# Laser_Array_Temp_V1_2.net
KiCad netlist of a schematic drawn in EAGLE
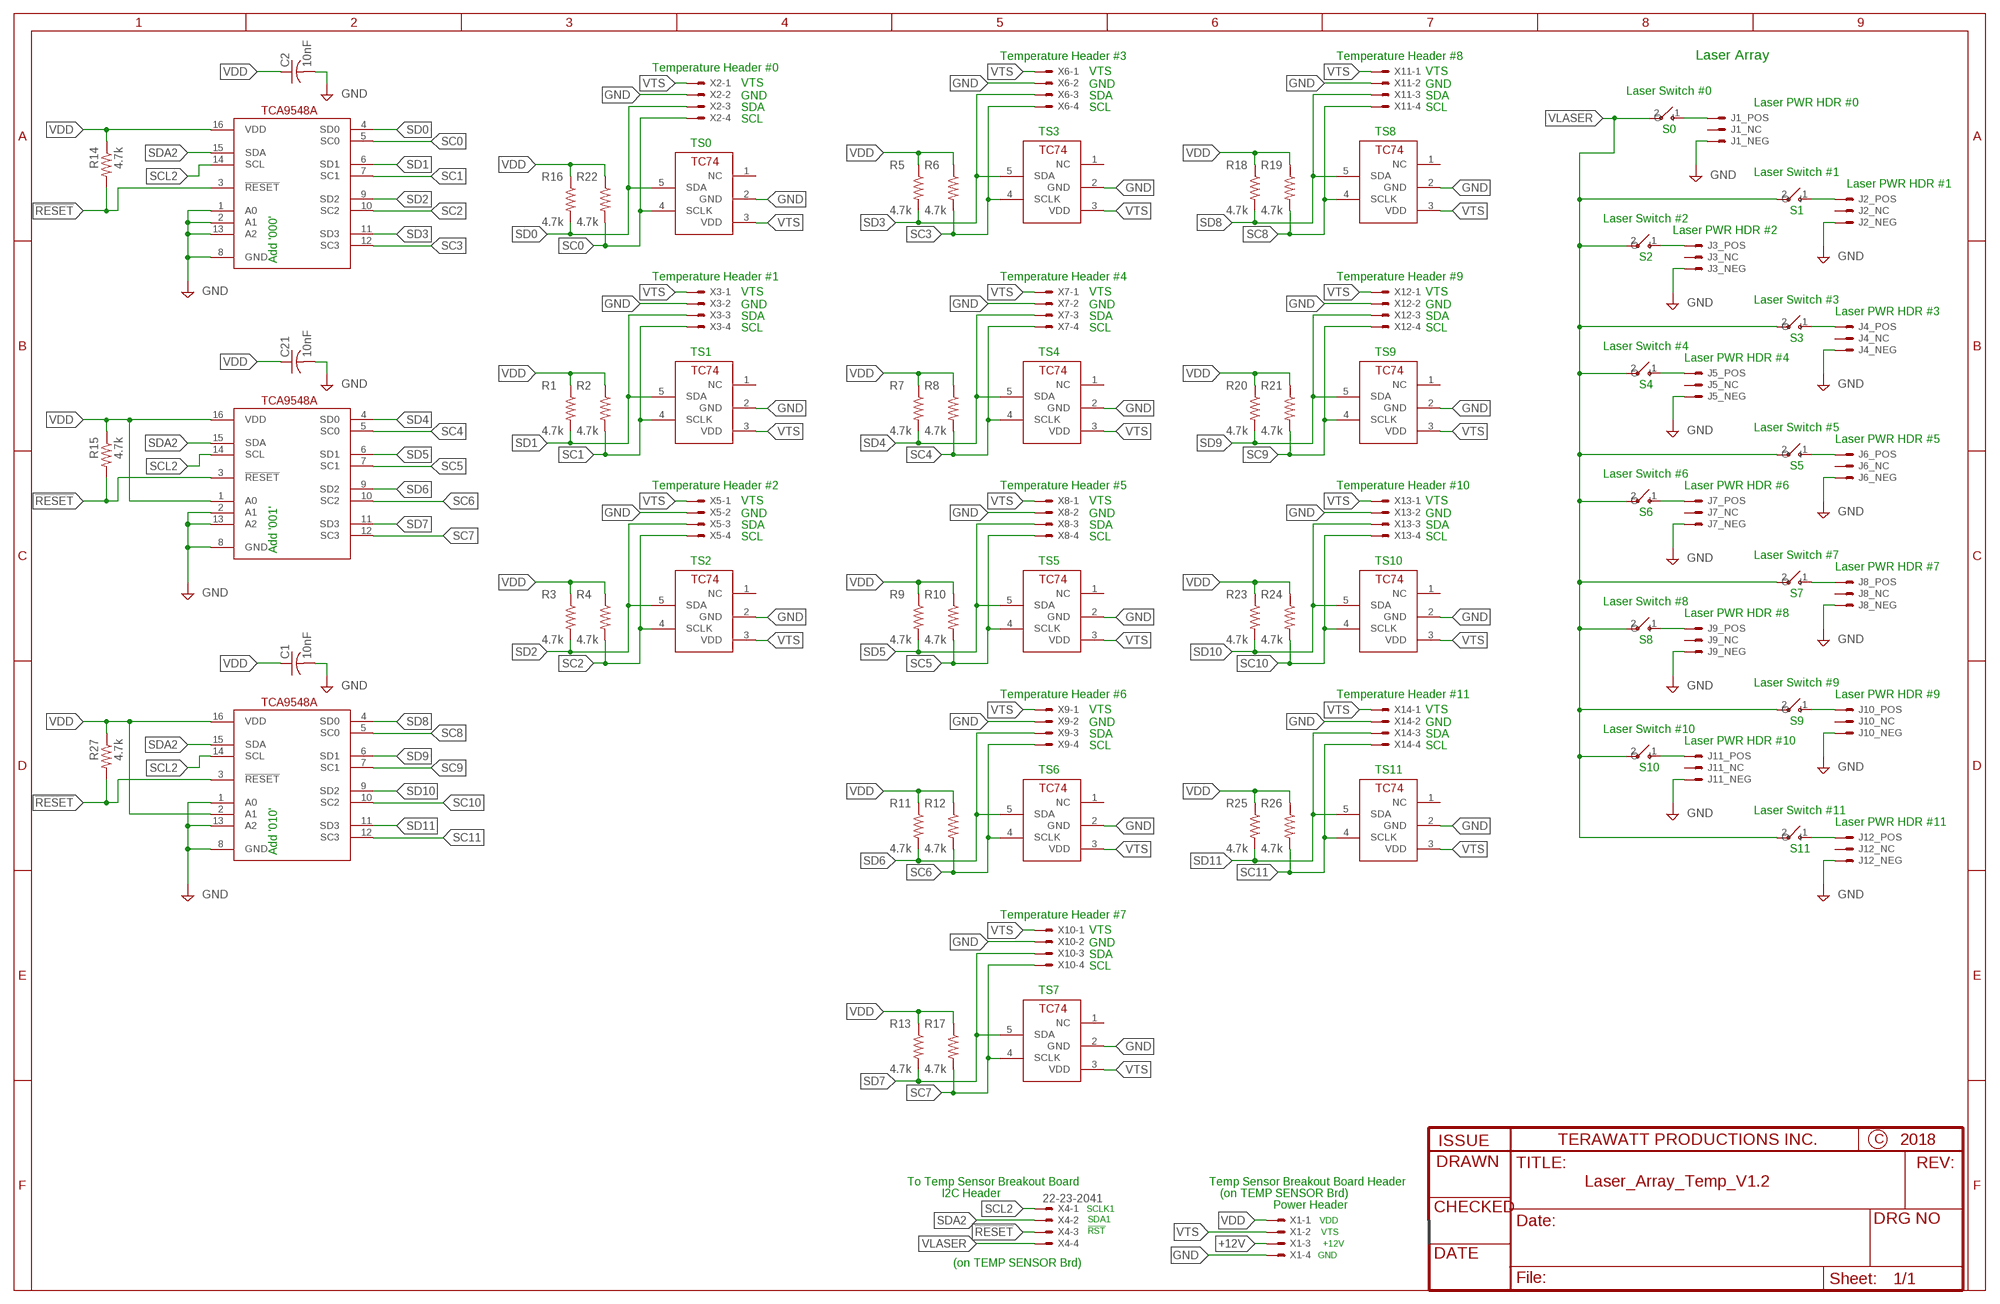
[diagram p0: schematic, sheet 1]

(export (version "E")
  (design (tool "Eeschema 10.0.6"))
  (components
    (comp (ref "C1")
      (value "10nF")
      (footprint "eagle-import:C0805")
      (libsource (lib "eagle-import") (part "C-USC0805"))
    )
    (comp (ref "C2")
      (value "10nF")
      (footprint "eagle-import:C0805")
      (libsource (lib "eagle-import") (part "C-USC0805"))
    )
    (comp (ref "C21")
      (value "10nF")
      (footprint "eagle-import:C0805")
      (libsource (lib "eagle-import") (part "C-USC0805"))
    )
    (comp (ref "J1")
      (value "LASER_MOD")
      (footprint "eagle-import:LASER_MOD")
      (libsource (lib "eagle-import") (part "LASER_MOD"))
    )
    (comp (ref "J2")
      (value "LASER_MOD")
      (footprint "eagle-import:LASER_MOD")
      (libsource (lib "eagle-import") (part "LASER_MOD"))
    )
    (comp (ref "J3")
      (value "LASER_MOD")
      (footprint "eagle-import:LASER_MOD")
      (libsource (lib "eagle-import") (part "LASER_MOD"))
    )
    (comp (ref "J4")
      (value "LASER_MOD")
      (footprint "eagle-import:LASER_MOD")
      (libsource (lib "eagle-import") (part "LASER_MOD"))
    )
    (comp (ref "J5")
      (value "LASER_MOD")
      (footprint "eagle-import:LASER_MOD")
      (libsource (lib "eagle-import") (part "LASER_MOD"))
    )
    (comp (ref "J6")
      (value "LASER_MOD")
      (footprint "eagle-import:LASER_MOD")
      (libsource (lib "eagle-import") (part "LASER_MOD"))
    )
    (comp (ref "J7")
      (value "LASER_MOD")
      (footprint "eagle-import:LASER_MOD")
      (libsource (lib "eagle-import") (part "LASER_MOD"))
    )
    (comp (ref "J8")
      (value "LASER_MOD")
      (footprint "eagle-import:LASER_MOD")
      (libsource (lib "eagle-import") (part "LASER_MOD"))
    )
    (comp (ref "J9")
      (value "LASER_MOD")
      (footprint "eagle-import:LASER_MOD")
      (libsource (lib "eagle-import") (part "LASER_MOD"))
    )
    (comp (ref "J10")
      (value "LASER_MOD")
      (footprint "eagle-import:LASER_MOD")
      (libsource (lib "eagle-import") (part "LASER_MOD"))
    )
    (comp (ref "J11")
      (value "LASER_MOD")
      (footprint "eagle-import:LASER_MOD")
      (libsource (lib "eagle-import") (part "LASER_MOD"))
    )
    (comp (ref "J12")
      (value "LASER_MOD")
      (footprint "eagle-import:LASER_MOD")
      (libsource (lib "eagle-import") (part "LASER_MOD"))
    )
    (comp (ref "R1")
      (value "4.7k")
      (footprint "eagle-import:M0805")
      (libsource (lib "eagle-import") (part "R-US_M0805"))
    )
    (comp (ref "R2")
      (value "4.7k")
      (footprint "eagle-import:M0805")
      (libsource (lib "eagle-import") (part "R-US_M0805"))
    )
    (comp (ref "R3")
      (value "4.7k")
      (footprint "eagle-import:M0805")
      (libsource (lib "eagle-import") (part "R-US_M0805"))
    )
    (comp (ref "R4")
      (value "4.7k")
      (footprint "eagle-import:M0805")
      (libsource (lib "eagle-import") (part "R-US_M0805"))
    )
    (comp (ref "R5")
      (value "4.7k")
      (footprint "eagle-import:M0805")
      (libsource (lib "eagle-import") (part "R-US_M0805"))
    )
    (comp (ref "R6")
      (value "4.7k")
      (footprint "eagle-import:M0805")
      (libsource (lib "eagle-import") (part "R-US_M0805"))
    )
    (comp (ref "R7")
      (value "4.7k")
      (footprint "eagle-import:M0805")
      (libsource (lib "eagle-import") (part "R-US_M0805"))
    )
    (comp (ref "R8")
      (value "4.7k")
      (footprint "eagle-import:M0805")
      (libsource (lib "eagle-import") (part "R-US_M0805"))
    )
    (comp (ref "R9")
      (value "4.7k")
      (footprint "eagle-import:M0805")
      (libsource (lib "eagle-import") (part "R-US_M0805"))
    )
    (comp (ref "R10")
      (value "4.7k")
      (footprint "eagle-import:M0805")
      (libsource (lib "eagle-import") (part "R-US_M0805"))
    )
    (comp (ref "R11")
      (value "4.7k")
      (footprint "eagle-import:M0805")
      (libsource (lib "eagle-import") (part "R-US_M0805"))
    )
    (comp (ref "R12")
      (value "4.7k")
      (footprint "eagle-import:M0805")
      (libsource (lib "eagle-import") (part "R-US_M0805"))
    )
    (comp (ref "R13")
      (value "4.7k")
      (footprint "eagle-import:M0805")
      (libsource (lib "eagle-import") (part "R-US_M0805"))
    )
    (comp (ref "R14")
      (value "4.7k")
      (footprint "eagle-import:M0805")
      (libsource (lib "eagle-import") (part "R-US_M0805"))
    )
    (comp (ref "R15")
      (value "4.7k")
      (footprint "eagle-import:M0805")
      (libsource (lib "eagle-import") (part "R-US_M0805"))
    )
    (comp (ref "R16")
      (value "4.7k")
      (footprint "eagle-import:M0805")
      (libsource (lib "eagle-import") (part "R-US_M0805"))
    )
    (comp (ref "R17")
      (value "4.7k")
      (footprint "eagle-import:M0805")
      (libsource (lib "eagle-import") (part "R-US_M0805"))
    )
    (comp (ref "R18")
      (value "4.7k")
      (footprint "eagle-import:M0805")
      (libsource (lib "eagle-import") (part "R-US_M0805"))
    )
    (comp (ref "R19")
      (value "4.7k")
      (footprint "eagle-import:M0805")
      (libsource (lib "eagle-import") (part "R-US_M0805"))
    )
    (comp (ref "R20")
      (value "4.7k")
      (footprint "eagle-import:M0805")
      (libsource (lib "eagle-import") (part "R-US_M0805"))
    )
    (comp (ref "R21")
      (value "4.7k")
      (footprint "eagle-import:M0805")
      (libsource (lib "eagle-import") (part "R-US_M0805"))
    )
    (comp (ref "R22")
      (value "4.7k")
      (footprint "eagle-import:M0805")
      (libsource (lib "eagle-import") (part "R-US_M0805"))
    )
    (comp (ref "R23")
      (value "4.7k")
      (footprint "eagle-import:M0805")
      (libsource (lib "eagle-import") (part "R-US_M0805"))
    )
    (comp (ref "R24")
      (value "4.7k")
      (footprint "eagle-import:M0805")
      (libsource (lib "eagle-import") (part "R-US_M0805"))
    )
    (comp (ref "R25")
      (value "4.7k")
      (footprint "eagle-import:M0805")
      (libsource (lib "eagle-import") (part "R-US_M0805"))
    )
    (comp (ref "R26")
      (value "4.7k")
      (footprint "eagle-import:M0805")
      (libsource (lib "eagle-import") (part "R-US_M0805"))
    )
    (comp (ref "R27")
      (value "4.7k")
      (footprint "eagle-import:M0805")
      (libsource (lib "eagle-import") (part "R-US_M0805"))
    )
    (comp (ref "S13")
      (value "TOGGLE_SPST")
      (footprint "eagle-import:22-23-2021")
      (libsource (lib "eagle-import") (part "TOGGLE_SPST"))
    )
    (comp (ref "S14")
      (value "TOGGLE_SPST")
      (footprint "eagle-import:22-23-2021")
      (libsource (lib "eagle-import") (part "TOGGLE_SPST"))
    )
    (comp (ref "S15")
      (value "TOGGLE_SPST")
      (footprint "eagle-import:22-23-2021")
      (libsource (lib "eagle-import") (part "TOGGLE_SPST"))
    )
    (comp (ref "S16")
      (value "TOGGLE_SPST")
      (footprint "eagle-import:22-23-2021")
      (libsource (lib "eagle-import") (part "TOGGLE_SPST"))
    )
    (comp (ref "S17")
      (value "TOGGLE_SPST")
      (footprint "eagle-import:22-23-2021")
      (libsource (lib "eagle-import") (part "TOGGLE_SPST"))
    )
    (comp (ref "S18")
      (value "TOGGLE_SPST")
      (footprint "eagle-import:22-23-2021")
      (libsource (lib "eagle-import") (part "TOGGLE_SPST"))
    )
    (comp (ref "S19")
      (value "TOGGLE_SPST")
      (footprint "eagle-import:22-23-2021")
      (libsource (lib "eagle-import") (part "TOGGLE_SPST"))
    )
    (comp (ref "S20")
      (value "TOGGLE_SPST")
      (footprint "eagle-import:22-23-2021")
      (libsource (lib "eagle-import") (part "TOGGLE_SPST"))
    )
    (comp (ref "S21")
      (value "TOGGLE_SPST")
      (footprint "eagle-import:22-23-2021")
      (libsource (lib "eagle-import") (part "TOGGLE_SPST"))
    )
    (comp (ref "S22")
      (value "TOGGLE_SPST")
      (footprint "eagle-import:22-23-2021")
      (libsource (lib "eagle-import") (part "TOGGLE_SPST"))
    )
    (comp (ref "S23")
      (value "TOGGLE_SPST")
      (footprint "eagle-import:22-23-2021")
      (libsource (lib "eagle-import") (part "TOGGLE_SPST"))
    )
    (comp (ref "S24")
      (value "TOGGLE_SPST")
      (footprint "eagle-import:22-23-2021")
      (libsource (lib "eagle-import") (part "TOGGLE_SPST"))
    )
    (comp (ref "TS1")
      (value "TC74")
      (footprint "eagle-import:SOT23-5L")
      (libsource (lib "eagle-import") (part "TC74"))
    )
    (comp (ref "TS2")
      (value "TC74")
      (footprint "eagle-import:SOT23-5L")
      (libsource (lib "eagle-import") (part "TC74"))
    )
    (comp (ref "TS3")
      (value "TC74")
      (footprint "eagle-import:SOT23-5L")
      (libsource (lib "eagle-import") (part "TC74"))
    )
    (comp (ref "TS4")
      (value "TC74")
      (footprint "eagle-import:SOT23-5L")
      (libsource (lib "eagle-import") (part "TC74"))
    )
    (comp (ref "TS5")
      (value "TC74")
      (footprint "eagle-import:SOT23-5L")
      (libsource (lib "eagle-import") (part "TC74"))
    )
    (comp (ref "TS6")
      (value "TC74")
      (footprint "eagle-import:SOT23-5L")
      (libsource (lib "eagle-import") (part "TC74"))
    )
    (comp (ref "TS7")
      (value "TC74")
      (footprint "eagle-import:SOT23-5L")
      (libsource (lib "eagle-import") (part "TC74"))
    )
    (comp (ref "TS8")
      (value "TC74")
      (footprint "eagle-import:SOT23-5L")
      (libsource (lib "eagle-import") (part "TC74"))
    )
    (comp (ref "TS9")
      (value "TC74")
      (footprint "eagle-import:SOT23-5L")
      (libsource (lib "eagle-import") (part "TC74"))
    )
    (comp (ref "TS10")
      (value "TC74")
      (footprint "eagle-import:SOT23-5L")
      (libsource (lib "eagle-import") (part "TC74"))
    )
    (comp (ref "TS11")
      (value "TC74")
      (footprint "eagle-import:SOT23-5L")
      (libsource (lib "eagle-import") (part "TC74"))
    )
    (comp (ref "TS12")
      (value "TC74")
      (footprint "eagle-import:SOT23-5L")
      (libsource (lib "eagle-import") (part "TC74"))
    )
    (comp (ref "U1")
      (value "TCA9546A")
      (footprint "eagle-import:SOIC16N")
      (libsource (lib "eagle-import") (part "TCA9546A"))
    )
    (comp (ref "U2")
      (value "TCA9546A")
      (footprint "eagle-import:SOIC16N")
      (libsource (lib "eagle-import") (part "TCA9546A"))
    )
    (comp (ref "U3")
      (value "TCA9546A")
      (footprint "eagle-import:SOIC16N")
      (libsource (lib "eagle-import") (part "TCA9546A"))
    )
    (comp (ref "X1")
      (value "22-23-2041")
      (footprint "eagle-import:22-23-2041")
      (fields (field (name "MF") "MOLEX"))
      (libsource (lib "eagle-import") (part "22-23-2041"))
    )
    (comp (ref "X2")
      (value "22-23-2041")
      (footprint "eagle-import:22-23-2041")
      (fields (field (name "MF") "MOLEX"))
      (libsource (lib "eagle-import") (part "22-23-2041"))
    )
    (comp (ref "X3")
      (value "22-23-2041")
      (footprint "eagle-import:22-23-2041")
      (fields (field (name "MF") "MOLEX"))
      (libsource (lib "eagle-import") (part "22-23-2041"))
    )
    (comp (ref "X4")
      (value "22-23-2041")
      (footprint "eagle-import:22-23-2041")
      (fields (field (name "MF") "MOLEX"))
      (libsource (lib "eagle-import") (part "22-23-2041"))
    )
    (comp (ref "X5")
      (value "22-23-2041")
      (footprint "eagle-import:22-23-2041")
      (fields (field (name "MF") "MOLEX"))
      (libsource (lib "eagle-import") (part "22-23-2041"))
    )
    (comp (ref "X6")
      (value "22-23-2041")
      (footprint "eagle-import:22-23-2041")
      (fields (field (name "MF") "MOLEX"))
      (libsource (lib "eagle-import") (part "22-23-2041"))
    )
    (comp (ref "X7")
      (value "22-23-2041")
      (footprint "eagle-import:22-23-2041")
      (fields (field (name "MF") "MOLEX"))
      (libsource (lib "eagle-import") (part "22-23-2041"))
    )
    (comp (ref "X8")
      (value "22-23-2041")
      (footprint "eagle-import:22-23-2041")
      (fields (field (name "MF") "MOLEX"))
      (libsource (lib "eagle-import") (part "22-23-2041"))
    )
    (comp (ref "X9")
      (value "22-23-2041")
      (footprint "eagle-import:22-23-2041")
      (fields (field (name "MF") "MOLEX"))
      (libsource (lib "eagle-import") (part "22-23-2041"))
    )
    (comp (ref "X10")
      (value "22-23-2041")
      (footprint "eagle-import:22-23-2041")
      (fields (field (name "MF") "MOLEX"))
      (libsource (lib "eagle-import") (part "22-23-2041"))
    )
    (comp (ref "X11")
      (value "22-23-2041")
      (footprint "eagle-import:22-23-2041")
      (fields (field (name "MF") "MOLEX"))
      (libsource (lib "eagle-import") (part "22-23-2041"))
    )
    (comp (ref "X12")
      (value "22-23-2041")
      (footprint "eagle-import:22-23-2041")
      (fields (field (name "MF") "MOLEX"))
      (libsource (lib "eagle-import") (part "22-23-2041"))
    )
    (comp (ref "X13")
      (value "22-23-2041")
      (footprint "eagle-import:22-23-2041")
      (fields (field (name "MF") "MOLEX"))
      (libsource (lib "eagle-import") (part "22-23-2041"))
    )
    (comp (ref "X14")
      (value "22-23-2041")
      (footprint "eagle-import:22-23-2041")
      (fields (field (name "MF") "MOLEX"))
      (libsource (lib "eagle-import") (part "22-23-2041"))
    )
  )
  (nets
    (net (code "1") (name "+12V") (class "Default")
      (node (ref "X1") (pin "3") (pinfunction "S_3") (pintype "passive"))
    )
    (net (code "2") (name "/~{RESET}") (class "Default")
      (node (ref "R14") (pin "2") (pinfunction "2_2") (pintype "passive"))
      (node (ref "R15") (pin "2") (pinfunction "2_2") (pintype "passive"))
      (node (ref "R27") (pin "2") (pinfunction "2_2") (pintype "passive"))
      (node (ref "U1") (pin "3") (pinfunction "~{RESET}_3") (pintype "bidirectional"))
      (node (ref "U2") (pin "3") (pinfunction "~{RESET}_3") (pintype "bidirectional"))
      (node (ref "U3") (pin "3") (pinfunction "~{RESET}_3") (pintype "bidirectional"))
      (node (ref "X4") (pin "3") (pinfunction "S_3") (pintype "passive"))
    )
    (net (code "3") (name "GND") (class "Default")
      (node (ref "C1") (pin "2") (pinfunction "2_2") (pintype "passive"))
      (node (ref "C2") (pin "2") (pinfunction "2_2") (pintype "passive"))
      (node (ref "C21") (pin "2") (pinfunction "2_2") (pintype "passive"))
      (node (ref "J1") (pin "3") (pinfunction "S_3") (pintype "passive"))
      (node (ref "J10") (pin "3") (pinfunction "S_3") (pintype "passive"))
      (node (ref "J11") (pin "3") (pinfunction "S_3") (pintype "passive"))
      (node (ref "J12") (pin "3") (pinfunction "S_3") (pintype "passive"))
      (node (ref "J2") (pin "3") (pinfunction "S_3") (pintype "passive"))
      (node (ref "J3") (pin "3") (pinfunction "S_3") (pintype "passive"))
      (node (ref "J4") (pin "3") (pinfunction "S_3") (pintype "passive"))
      (node (ref "J5") (pin "3") (pinfunction "S_3") (pintype "passive"))
      (node (ref "J6") (pin "3") (pinfunction "S_3") (pintype "passive"))
      (node (ref "J7") (pin "3") (pinfunction "S_3") (pintype "passive"))
      (node (ref "J8") (pin "3") (pinfunction "S_3") (pintype "passive"))
      (node (ref "J9") (pin "3") (pinfunction "S_3") (pintype "passive"))
      (node (ref "TS1") (pin "2") (pinfunction "GND_2") (pintype "bidirectional"))
      (node (ref "TS10") (pin "2") (pinfunction "GND_2") (pintype "bidirectional"))
      (node (ref "TS11") (pin "2") (pinfunction "GND_2") (pintype "bidirectional"))
      (node (ref "TS12") (pin "2") (pinfunction "GND_2") (pintype "bidirectional"))
      (node (ref "TS2") (pin "2") (pinfunction "GND_2") (pintype "bidirectional"))
      (node (ref "TS3") (pin "2") (pinfunction "GND_2") (pintype "bidirectional"))
      (node (ref "TS4") (pin "2") (pinfunction "GND_2") (pintype "bidirectional"))
      (node (ref "TS5") (pin "2") (pinfunction "GND_2") (pintype "bidirectional"))
      (node (ref "TS6") (pin "2") (pinfunction "GND_2") (pintype "bidirectional"))
      (node (ref "TS7") (pin "2") (pinfunction "GND_2") (pintype "bidirectional"))
      (node (ref "TS8") (pin "2") (pinfunction "GND_2") (pintype "bidirectional"))
      (node (ref "TS9") (pin "2") (pinfunction "GND_2") (pintype "bidirectional"))
      (node (ref "U1") (pin "1") (pinfunction "A0_1") (pintype "bidirectional"))
      (node (ref "U1") (pin "13") (pinfunction "A2_13") (pintype "bidirectional"))
      (node (ref "U1") (pin "2") (pinfunction "A1_2") (pintype "bidirectional"))
      (node (ref "U1") (pin "8") (pinfunction "GND_8") (pintype "bidirectional"))
      (node (ref "U2") (pin "13") (pinfunction "A2_13") (pintype "bidirectional"))
      (node (ref "U2") (pin "2") (pinfunction "A1_2") (pintype "bidirectional"))
      (node (ref "U2") (pin "8") (pinfunction "GND_8") (pintype "bidirectional"))
      (node (ref "U3") (pin "1") (pinfunction "A0_1") (pintype "bidirectional"))
      (node (ref "U3") (pin "13") (pinfunction "A2_13") (pintype "bidirectional"))
      (node (ref "U3") (pin "8") (pinfunction "GND_8") (pintype "bidirectional"))
      (node (ref "X1") (pin "4") (pinfunction "S_4") (pintype "passive"))
      (node (ref "X10") (pin "2") (pinfunction "S_2") (pintype "passive"))
      (node (ref "X11") (pin "2") (pinfunction "S_2") (pintype "passive"))
      (node (ref "X12") (pin "2") (pinfunction "S_2") (pintype "passive"))
      (node (ref "X13") (pin "2") (pinfunction "S_2") (pintype "passive"))
      (node (ref "X14") (pin "2") (pinfunction "S_2") (pintype "passive"))
      (node (ref "X2") (pin "2") (pinfunction "S_2") (pintype "passive"))
      (node (ref "X3") (pin "2") (pinfunction "S_2") (pintype "passive"))
      (node (ref "X5") (pin "2") (pinfunction "S_2") (pintype "passive"))
      (node (ref "X6") (pin "2") (pinfunction "S_2") (pintype "passive"))
      (node (ref "X7") (pin "2") (pinfunction "S_2") (pintype "passive"))
      (node (ref "X8") (pin "2") (pinfunction "S_2") (pintype "passive"))
      (node (ref "X9") (pin "2") (pinfunction "S_2") (pintype "passive"))
    )
    (net (code "4") (name "Net-(J1C-S)") (class "Default")
      (node (ref "J1") (pin "1") (pinfunction "S_1") (pintype "passive"))
      (node (ref "S16") (pin "1") (pinfunction "O_1") (pintype "bidirectional"))
    )
    (net (code "5") (name "Net-(J2C-S)") (class "Default")
      (node (ref "J2") (pin "1") (pinfunction "S_1") (pintype "passive"))
      (node (ref "S13") (pin "1") (pinfunction "O_1") (pintype "bidirectional"))
    )
    (net (code "6") (name "Net-(J3C-S)") (class "Default")
      (node (ref "J3") (pin "1") (pinfunction "S_1") (pintype "passive"))
      (node (ref "S14") (pin "1") (pinfunction "O_1") (pintype "bidirectional"))
    )
    (net (code "7") (name "Net-(J4C-S)") (class "Default")
      (node (ref "J4") (pin "1") (pinfunction "S_1") (pintype "passive"))
      (node (ref "S15") (pin "1") (pinfunction "O_1") (pintype "bidirectional"))
    )
    (net (code "8") (name "Net-(J5C-S)") (class "Default")
      (node (ref "J5") (pin "1") (pinfunction "S_1") (pintype "passive"))
      (node (ref "S17") (pin "1") (pinfunction "O_1") (pintype "bidirectional"))
    )
    (net (code "9") (name "Net-(J6C-S)") (class "Default")
      (node (ref "J6") (pin "1") (pinfunction "S_1") (pintype "passive"))
      (node (ref "S18") (pin "1") (pinfunction "O_1") (pintype "bidirectional"))
    )
    (net (code "10") (name "Net-(J7C-S)") (class "Default")
      (node (ref "J7") (pin "1") (pinfunction "S_1") (pintype "passive"))
      (node (ref "S19") (pin "1") (pinfunction "O_1") (pintype "bidirectional"))
    )
    (net (code "11") (name "Net-(J8C-S)") (class "Default")
      (node (ref "J8") (pin "1") (pinfunction "S_1") (pintype "passive"))
      (node (ref "S20") (pin "1") (pinfunction "O_1") (pintype "bidirectional"))
    )
    (net (code "12") (name "Net-(J9C-S)") (class "Default")
      (node (ref "J9") (pin "1") (pinfunction "S_1") (pintype "passive"))
      (node (ref "S21") (pin "1") (pinfunction "O_1") (pintype "bidirectional"))
    )
    (net (code "13") (name "Net-(J10C-S)") (class "Default")
      (node (ref "J10") (pin "1") (pinfunction "S_1") (pintype "passive"))
      (node (ref "S22") (pin "1") (pinfunction "O_1") (pintype "bidirectional"))
    )
    (net (code "14") (name "Net-(J11C-S)") (class "Default")
      (node (ref "J11") (pin "1") (pinfunction "S_1") (pintype "passive"))
      (node (ref "S23") (pin "1") (pinfunction "O_1") (pintype "bidirectional"))
    )
    (net (code "15") (name "Net-(J12C-S)") (class "Default")
      (node (ref "J12") (pin "1") (pinfunction "S_1") (pintype "passive"))
      (node (ref "S24") (pin "1") (pinfunction "O_1") (pintype "bidirectional"))
    )
    (net (code "16") (name "SC0") (class "Default")
      (node (ref "R22") (pin "2") (pinfunction "2_2") (pintype "passive"))
      (node (ref "TS1") (pin "4") (pinfunction "SCLK_4") (pintype "bidirectional"))
      (node (ref "U1") (pin "5") (pinfunction "SC0_5") (pintype "bidirectional"))
      (node (ref "X2") (pin "4") (pinfunction "S_4") (pintype "passive"))
    )
    (net (code "17") (name "SC1") (class "Default")
      (node (ref "R2") (pin "2") (pinfunction "2_2") (pintype "passive"))
      (node (ref "TS2") (pin "4") (pinfunction "SCLK_4") (pintype "bidirectional"))
      (node (ref "U1") (pin "7") (pinfunction "SC1_7") (pintype "bidirectional"))
      (node (ref "X3") (pin "4") (pinfunction "S_4") (pintype "passive"))
    )
    (net (code "18") (name "SC2") (class "Default")
      (node (ref "R4") (pin "2") (pinfunction "2_2") (pintype "passive"))
      (node (ref "TS3") (pin "4") (pinfunction "SCLK_4") (pintype "bidirectional"))
      (node (ref "U1") (pin "10") (pinfunction "SC2_10") (pintype "bidirectional"))
      (node (ref "X5") (pin "4") (pinfunction "S_4") (pintype "passive"))
    )
    (net (code "19") (name "SC3") (class "Default")
      (node (ref "R6") (pin "2") (pinfunction "2_2") (pintype "passive"))
      (node (ref "TS4") (pin "4") (pinfunction "SCLK_4") (pintype "bidirectional"))
      (node (ref "U1") (pin "12") (pinfunction "SC3_12") (pintype "bidirectional"))
      (node (ref "X6") (pin "4") (pinfunction "S_4") (pintype "passive"))
    )
    (net (code "20") (name "SC4") (class "Default")
      (node (ref "R8") (pin "2") (pinfunction "2_2") (pintype "passive"))
      (node (ref "TS5") (pin "4") (pinfunction "SCLK_4") (pintype "bidirectional"))
      (node (ref "U2") (pin "5") (pinfunction "SC0_5") (pintype "bidirectional"))
      (node (ref "X7") (pin "4") (pinfunction "S_4") (pintype "passive"))
    )
    (net (code "21") (name "SC5") (class "Default")
      (node (ref "R10") (pin "2") (pinfunction "2_2") (pintype "passive"))
      (node (ref "TS6") (pin "4") (pinfunction "SCLK_4") (pintype "bidirectional"))
      (node (ref "U2") (pin "7") (pinfunction "SC1_7") (pintype "bidirectional"))
      (node (ref "X8") (pin "4") (pinfunction "S_4") (pintype "passive"))
    )
    (net (code "22") (name "SC6") (class "Default")
      (node (ref "R12") (pin "2") (pinfunction "2_2") (pintype "passive"))
      (node (ref "TS7") (pin "4") (pinfunction "SCLK_4") (pintype "bidirectional"))
      (node (ref "U2") (pin "10") (pinfunction "SC2_10") (pintype "bidirectional"))
      (node (ref "X9") (pin "4") (pinfunction "S_4") (pintype "passive"))
    )
    (net (code "23") (name "SC7") (class "Default")
      (node (ref "R17") (pin "2") (pinfunction "2_2") (pintype "passive"))
      (node (ref "TS8") (pin "4") (pinfunction "SCLK_4") (pintype "bidirectional"))
      (node (ref "U2") (pin "12") (pinfunction "SC3_12") (pintype "bidirectional"))
      (node (ref "X10") (pin "4") (pinfunction "S_4") (pintype "passive"))
    )
    (net (code "24") (name "SC8") (class "Default")
      (node (ref "R19") (pin "2") (pinfunction "2_2") (pintype "passive"))
      (node (ref "TS9") (pin "4") (pinfunction "SCLK_4") (pintype "bidirectional"))
      (node (ref "U3") (pin "5") (pinfunction "SC0_5") (pintype "bidirectional"))
      (node (ref "X11") (pin "4") (pinfunction "S_4") (pintype "passive"))
    )
    (net (code "25") (name "SC9") (class "Default")
      (node (ref "R21") (pin "2") (pinfunction "2_2") (pintype "passive"))
      (node (ref "TS10") (pin "4") (pinfunction "SCLK_4") (pintype "bidirectional"))
      (node (ref "U3") (pin "7") (pinfunction "SC1_7") (pintype "bidirectional"))
      (node (ref "X12") (pin "4") (pinfunction "S_4") (pintype "passive"))
    )
    (net (code "26") (name "SC10") (class "Default")
      (node (ref "R24") (pin "2") (pinfunction "2_2") (pintype "passive"))
      (node (ref "TS11") (pin "4") (pinfunction "SCLK_4") (pintype "bidirectional"))
      (node (ref "U3") (pin "10") (pinfunction "SC2_10") (pintype "bidirectional"))
      (node (ref "X13") (pin "4") (pinfunction "S_4") (pintype "passive"))
    )
    (net (code "27") (name "SC11") (class "Default")
      (node (ref "R26") (pin "2") (pinfunction "2_2") (pintype "passive"))
      (node (ref "TS12") (pin "4") (pinfunction "SCLK_4") (pintype "bidirectional"))
      (node (ref "U3") (pin "12") (pinfunction "SC3_12") (pintype "bidirectional"))
      (node (ref "X14") (pin "4") (pinfunction "S_4") (pintype "passive"))
    )
    (net (code "28") (name "SCL2") (class "Default")
      (node (ref "U1") (pin "14") (pinfunction "SCL_14") (pintype "bidirectional"))
      (node (ref "U2") (pin "14") (pinfunction "SCL_14") (pintype "bidirectional"))
      (node (ref "U3") (pin "14") (pinfunction "SCL_14") (pintype "bidirectional"))
      (node (ref "X4") (pin "1") (pinfunction "S_1") (pintype "passive"))
    )
    (net (code "29") (name "SD0") (class "Default")
      (node (ref "R16") (pin "2") (pinfunction "2_2") (pintype "passive"))
      (node (ref "TS1") (pin "5") (pinfunction "SDA_5") (pintype "bidirectional"))
      (node (ref "U1") (pin "4") (pinfunction "SD0_4") (pintype "bidirectional"))
      (node (ref "X2") (pin "3") (pinfunction "S_3") (pintype "passive"))
    )
    (net (code "30") (name "SD1") (class "Default")
      (node (ref "R1") (pin "2") (pinfunction "2_2") (pintype "passive"))
      (node (ref "TS2") (pin "5") (pinfunction "SDA_5") (pintype "bidirectional"))
      (node (ref "U1") (pin "6") (pinfunction "SD1_6") (pintype "bidirectional"))
      (node (ref "X3") (pin "3") (pinfunction "S_3") (pintype "passive"))
    )
    (net (code "31") (name "SD2") (class "Default")
      (node (ref "R3") (pin "2") (pinfunction "2_2") (pintype "passive"))
      (node (ref "TS3") (pin "5") (pinfunction "SDA_5") (pintype "bidirectional"))
      (node (ref "U1") (pin "9") (pinfunction "SD2_9") (pintype "bidirectional"))
      (node (ref "X5") (pin "3") (pinfunction "S_3") (pintype "passive"))
    )
    (net (code "32") (name "SD3") (class "Default")
      (node (ref "R5") (pin "2") (pinfunction "2_2") (pintype "passive"))
      (node (ref "TS4") (pin "5") (pinfunction "SDA_5") (pintype "bidirectional"))
      (node (ref "U1") (pin "11") (pinfunction "SD3_11") (pintype "bidirectional"))
      (node (ref "X6") (pin "3") (pinfunction "S_3") (pintype "passive"))
    )
    (net (code "33") (name "SD4") (class "Default")
      (node (ref "R7") (pin "2") (pinfunction "2_2") (pintype "passive"))
      (node (ref "TS5") (pin "5") (pinfunction "SDA_5") (pintype "bidirectional"))
      (node (ref "U2") (pin "4") (pinfunction "SD0_4") (pintype "bidirectional"))
      (node (ref "X7") (pin "3") (pinfunction "S_3") (pintype "passive"))
    )
    (net (code "34") (name "SD5") (class "Default")
      (node (ref "R9") (pin "2") (pinfunction "2_2") (pintype "passive"))
      (node (ref "TS6") (pin "5") (pinfunction "SDA_5") (pintype "bidirectional"))
      (node (ref "U2") (pin "6") (pinfunction "SD1_6") (pintype "bidirectional"))
      (node (ref "X8") (pin "3") (pinfunction "S_3") (pintype "passive"))
    )
    (net (code "35") (name "SD6") (class "Default")
      (node (ref "R11") (pin "2") (pinfunction "2_2") (pintype "passive"))
      (node (ref "TS7") (pin "5") (pinfunction "SDA_5") (pintype "bidirectional"))
      (node (ref "U2") (pin "9") (pinfunction "SD2_9") (pintype "bidirectional"))
      (node (ref "X9") (pin "3") (pinfunction "S_3") (pintype "passive"))
    )
    (net (code "36") (name "SD7") (class "Default")
      (node (ref "R13") (pin "2") (pinfunction "2_2") (pintype "passive"))
      (node (ref "TS8") (pin "5") (pinfunction "SDA_5") (pintype "bidirectional"))
      (node (ref "U2") (pin "11") (pinfunction "SD3_11") (pintype "bidirectional"))
      (node (ref "X10") (pin "3") (pinfunction "S_3") (pintype "passive"))
    )
    (net (code "37") (name "SD8") (class "Default")
      (node (ref "R18") (pin "2") (pinfunction "2_2") (pintype "passive"))
      (node (ref "TS9") (pin "5") (pinfunction "SDA_5") (pintype "bidirectional"))
      (node (ref "U3") (pin "4") (pinfunction "SD0_4") (pintype "bidirectional"))
      (node (ref "X11") (pin "3") (pinfunction "S_3") (pintype "passive"))
    )
    (net (code "38") (name "SD9") (class "Default")
      (node (ref "R20") (pin "2") (pinfunction "2_2") (pintype "passive"))
      (node (ref "TS10") (pin "5") (pinfunction "SDA_5") (pintype "bidirectional"))
      (node (ref "U3") (pin "6") (pinfunction "SD1_6") (pintype "bidirectional"))
      (node (ref "X12") (pin "3") (pinfunction "S_3") (pintype "passive"))
    )
    (net (code "39") (name "SD10") (class "Default")
      (node (ref "R23") (pin "2") (pinfunction "2_2") (pintype "passive"))
      (node (ref "TS11") (pin "5") (pinfunction "SDA_5") (pintype "bidirectional"))
      (node (ref "U3") (pin "9") (pinfunction "SD2_9") (pintype "bidirectional"))
      (node (ref "X13") (pin "3") (pinfunction "S_3") (pintype "passive"))
    )
    (net (code "40") (name "SD11") (class "Default")
      (node (ref "R25") (pin "2") (pinfunction "2_2") (pintype "passive"))
      (node (ref "TS12") (pin "5") (pinfunction "SDA_5") (pintype "bidirectional"))
      (node (ref "U3") (pin "11") (pinfunction "SD3_11") (pintype "bidirectional"))
      (node (ref "X14") (pin "3") (pinfunction "S_3") (pintype "passive"))
    )
    (net (code "41") (name "SDA2") (class "Default")
      (node (ref "U1") (pin "15") (pinfunction "SDA_15") (pintype "bidirectional"))
      (node (ref "U2") (pin "15") (pinfunction "SDA_15") (pintype "bidirectional"))
      (node (ref "U3") (pin "15") (pinfunction "SDA_15") (pintype "bidirectional"))
      (node (ref "X4") (pin "2") (pinfunction "S_2") (pintype "passive"))
    )
    (net (code "42") (name "VDD") (class "Default")
      (node (ref "C1") (pin "1") (pinfunction "1_1") (pintype "passive"))
      (node (ref "C2") (pin "1") (pinfunction "1_1") (pintype "passive"))
      (node (ref "C21") (pin "1") (pinfunction "1_1") (pintype "passive"))
      (node (ref "R1") (pin "1") (pinfunction "1_1") (pintype "passive"))
      (node (ref "R10") (pin "1") (pinfunction "1_1") (pintype "passive"))
      (node (ref "R11") (pin "1") (pinfunction "1_1") (pintype "passive"))
      (node (ref "R12") (pin "1") (pinfunction "1_1") (pintype "passive"))
      (node (ref "R13") (pin "1") (pinfunction "1_1") (pintype "passive"))
      (node (ref "R14") (pin "1") (pinfunction "1_1") (pintype "passive"))
      (node (ref "R15") (pin "1") (pinfunction "1_1") (pintype "passive"))
      (node (ref "R16") (pin "1") (pinfunction "1_1") (pintype "passive"))
      (node (ref "R17") (pin "1") (pinfunction "1_1") (pintype "passive"))
      (node (ref "R18") (pin "1") (pinfunction "1_1") (pintype "passive"))
      (node (ref "R19") (pin "1") (pinfunction "1_1") (pintype "passive"))
      (node (ref "R2") (pin "1") (pinfunction "1_1") (pintype "passive"))
      (node (ref "R20") (pin "1") (pinfunction "1_1") (pintype "passive"))
      (node (ref "R21") (pin "1") (pinfunction "1_1") (pintype "passive"))
      (node (ref "R22") (pin "1") (pinfunction "1_1") (pintype "passive"))
      (node (ref "R23") (pin "1") (pinfunction "1_1") (pintype "passive"))
      (node (ref "R24") (pin "1") (pinfunction "1_1") (pintype "passive"))
      (node (ref "R25") (pin "1") (pinfunction "1_1") (pintype "passive"))
      (node (ref "R26") (pin "1") (pinfunction "1_1") (pintype "passive"))
      (node (ref "R27") (pin "1") (pinfunction "1_1") (pintype "passive"))
      (node (ref "R3") (pin "1") (pinfunction "1_1") (pintype "passive"))
      (node (ref "R4") (pin "1") (pinfunction "1_1") (pintype "passive"))
      (node (ref "R5") (pin "1") (pinfunction "1_1") (pintype "passive"))
      (node (ref "R6") (pin "1") (pinfunction "1_1") (pintype "passive"))
      (node (ref "R7") (pin "1") (pinfunction "1_1") (pintype "passive"))
      (node (ref "R8") (pin "1") (pinfunction "1_1") (pintype "passive"))
      (node (ref "R9") (pin "1") (pinfunction "1_1") (pintype "passive"))
      (node (ref "U1") (pin "16") (pinfunction "VDD_16") (pintype "bidirectional"))
      (node (ref "U2") (pin "1") (pinfunction "A0_1") (pintype "bidirectional"))
      (node (ref "U2") (pin "16") (pinfunction "VDD_16") (pintype "bidirectional"))
      (node (ref "U3") (pin "16") (pinfunction "VDD_16") (pintype "bidirectional"))
      (node (ref "U3") (pin "2") (pinfunction "A1_2") (pintype "bidirectional"))
      (node (ref "X1") (pin "1") (pinfunction "S_1") (pintype "passive"))
    )
    (net (code "43") (name "VLASER") (class "Default")
      (node (ref "S13") (pin "2") (pinfunction "I_2") (pintype "bidirectional"))
      (node (ref "S14") (pin "2") (pinfunction "I_2") (pintype "bidirectional"))
      (node (ref "S15") (pin "2") (pinfunction "I_2") (pintype "bidirectional"))
      (node (ref "S16") (pin "2") (pinfunction "I_2") (pintype "bidirectional"))
      (node (ref "S17") (pin "2") (pinfunction "I_2") (pintype "bidirectional"))
      (node (ref "S18") (pin "2") (pinfunction "I_2") (pintype "bidirectional"))
      (node (ref "S19") (pin "2") (pinfunction "I_2") (pintype "bidirectional"))
      (node (ref "S20") (pin "2") (pinfunction "I_2") (pintype "bidirectional"))
      (node (ref "S21") (pin "2") (pinfunction "I_2") (pintype "bidirectional"))
      (node (ref "S22") (pin "2") (pinfunction "I_2") (pintype "bidirectional"))
      (node (ref "S23") (pin "2") (pinfunction "I_2") (pintype "bidirectional"))
      (node (ref "S24") (pin "2") (pinfunction "I_2") (pintype "bidirectional"))
      (node (ref "X4") (pin "4") (pinfunction "S_4") (pintype "passive"))
    )
    (net (code "44") (name "VTS") (class "Default")
      (node (ref "TS1") (pin "3") (pinfunction "VDD_3") (pintype "bidirectional"))
      (node (ref "TS10") (pin "3") (pinfunction "VDD_3") (pintype "bidirectional"))
      (node (ref "TS11") (pin "3") (pinfunction "VDD_3") (pintype "bidirectional"))
      (node (ref "TS12") (pin "3") (pinfunction "VDD_3") (pintype "bidirectional"))
      (node (ref "TS2") (pin "3") (pinfunction "VDD_3") (pintype "bidirectional"))
      (node (ref "TS3") (pin "3") (pinfunction "VDD_3") (pintype "bidirectional"))
      (node (ref "TS4") (pin "3") (pinfunction "VDD_3") (pintype "bidirectional"))
      (node (ref "TS5") (pin "3") (pinfunction "VDD_3") (pintype "bidirectional"))
      (node (ref "TS6") (pin "3") (pinfunction "VDD_3") (pintype "bidirectional"))
      (node (ref "TS7") (pin "3") (pinfunction "VDD_3") (pintype "bidirectional"))
      (node (ref "TS8") (pin "3") (pinfunction "VDD_3") (pintype "bidirectional"))
      (node (ref "TS9") (pin "3") (pinfunction "VDD_3") (pintype "bidirectional"))
      (node (ref "X1") (pin "2") (pinfunction "S_2") (pintype "passive"))
      (node (ref "X10") (pin "1") (pinfunction "S_1") (pintype "passive"))
      (node (ref "X11") (pin "1") (pinfunction "S_1") (pintype "passive"))
      (node (ref "X12") (pin "1") (pinfunction "S_1") (pintype "passive"))
      (node (ref "X13") (pin "1") (pinfunction "S_1") (pintype "passive"))
      (node (ref "X14") (pin "1") (pinfunction "S_1") (pintype "passive"))
      (node (ref "X2") (pin "1") (pinfunction "S_1") (pintype "passive"))
      (node (ref "X3") (pin "1") (pinfunction "S_1") (pintype "passive"))
      (node (ref "X5") (pin "1") (pinfunction "S_1") (pintype "passive"))
      (node (ref "X6") (pin "1") (pinfunction "S_1") (pintype "passive"))
      (node (ref "X7") (pin "1") (pinfunction "S_1") (pintype "passive"))
      (node (ref "X8") (pin "1") (pinfunction "S_1") (pintype "passive"))
      (node (ref "X9") (pin "1") (pinfunction "S_1") (pintype "passive"))
    )
    (net (code "45") (name "unconnected-(J1A-S-Pad2)") (class "Default")
      (node (ref "J1") (pin "2") (pinfunction "S_2") (pintype "passive"))
    )
    (net (code "46") (name "unconnected-(J2A-S-Pad2)") (class "Default")
      (node (ref "J2") (pin "2") (pinfunction "S_2") (pintype "passive"))
    )
    (net (code "47") (name "unconnected-(J3A-S-Pad2)") (class "Default")
      (node (ref "J3") (pin "2") (pinfunction "S_2") (pintype "passive"))
    )
    (net (code "48") (name "unconnected-(J4A-S-Pad2)") (class "Default")
      (node (ref "J4") (pin "2") (pinfunction "S_2") (pintype "passive"))
    )
    (net (code "49") (name "unconnected-(J5A-S-Pad2)") (class "Default")
      (node (ref "J5") (pin "2") (pinfunction "S_2") (pintype "passive"))
    )
    (net (code "50") (name "unconnected-(J6A-S-Pad2)") (class "Default")
      (node (ref "J6") (pin "2") (pinfunction "S_2") (pintype "passive"))
    )
    (net (code "51") (name "unconnected-(J7A-S-Pad2)") (class "Default")
      (node (ref "J7") (pin "2") (pinfunction "S_2") (pintype "passive"))
    )
    (net (code "52") (name "unconnected-(J8A-S-Pad2)") (class "Default")
      (node (ref "J8") (pin "2") (pinfunction "S_2") (pintype "passive"))
    )
    (net (code "53") (name "unconnected-(J9A-S-Pad2)") (class "Default")
      (node (ref "J9") (pin "2") (pinfunction "S_2") (pintype "passive"))
    )
    (net (code "54") (name "unconnected-(J10A-S-Pad2)") (class "Default")
      (node (ref "J10") (pin "2") (pinfunction "S_2") (pintype "passive"))
    )
    (net (code "55") (name "unconnected-(J11A-S-Pad2)") (class "Default")
      (node (ref "J11") (pin "2") (pinfunction "S_2") (pintype "passive"))
    )
    (net (code "56") (name "unconnected-(J12A-S-Pad2)") (class "Default")
      (node (ref "J12") (pin "2") (pinfunction "S_2") (pintype "passive"))
    )
    (net (code "57") (name "unconnected-(TS1-NC-Pad1)") (class "Default")
      (node (ref "TS1") (pin "1") (pinfunction "NC_1") (pintype "bidirectional"))
    )
    (net (code "58") (name "unconnected-(TS2-NC-Pad1)") (class "Default")
      (node (ref "TS2") (pin "1") (pinfunction "NC_1") (pintype "bidirectional"))
    )
    (net (code "59") (name "unconnected-(TS3-NC-Pad1)") (class "Default")
      (node (ref "TS3") (pin "1") (pinfunction "NC_1") (pintype "bidirectional"))
    )
    (net (code "60") (name "unconnected-(TS4-NC-Pad1)") (class "Default")
      (node (ref "TS4") (pin "1") (pinfunction "NC_1") (pintype "bidirectional"))
    )
    (net (code "61") (name "unconnected-(TS5-NC-Pad1)") (class "Default")
      (node (ref "TS5") (pin "1") (pinfunction "NC_1") (pintype "bidirectional"))
    )
    (net (code "62") (name "unconnected-(TS6-NC-Pad1)") (class "Default")
      (node (ref "TS6") (pin "1") (pinfunction "NC_1") (pintype "bidirectional"))
    )
    (net (code "63") (name "unconnected-(TS7-NC-Pad1)") (class "Default")
      (node (ref "TS7") (pin "1") (pinfunction "NC_1") (pintype "bidirectional"))
    )
    (net (code "64") (name "unconnected-(TS8-NC-Pad1)") (class "Default")
      (node (ref "TS8") (pin "1") (pinfunction "NC_1") (pintype "bidirectional"))
    )
    (net (code "65") (name "unconnected-(TS9-NC-Pad1)") (class "Default")
      (node (ref "TS9") (pin "1") (pinfunction "NC_1") (pintype "bidirectional"))
    )
    (net (code "66") (name "unconnected-(TS10-NC-Pad1)") (class "Default")
      (node (ref "TS10") (pin "1") (pinfunction "NC_1") (pintype "bidirectional"))
    )
    (net (code "67") (name "unconnected-(TS11-NC-Pad1)") (class "Default")
      (node (ref "TS11") (pin "1") (pinfunction "NC_1") (pintype "bidirectional"))
    )
    (net (code "68") (name "unconnected-(TS12-NC-Pad1)") (class "Default")
      (node (ref "TS12") (pin "1") (pinfunction "NC_1") (pintype "bidirectional"))
    )
  )
)
